# zgrzewarka.net
KiCad netlist of a schematic drawn in EAGLE
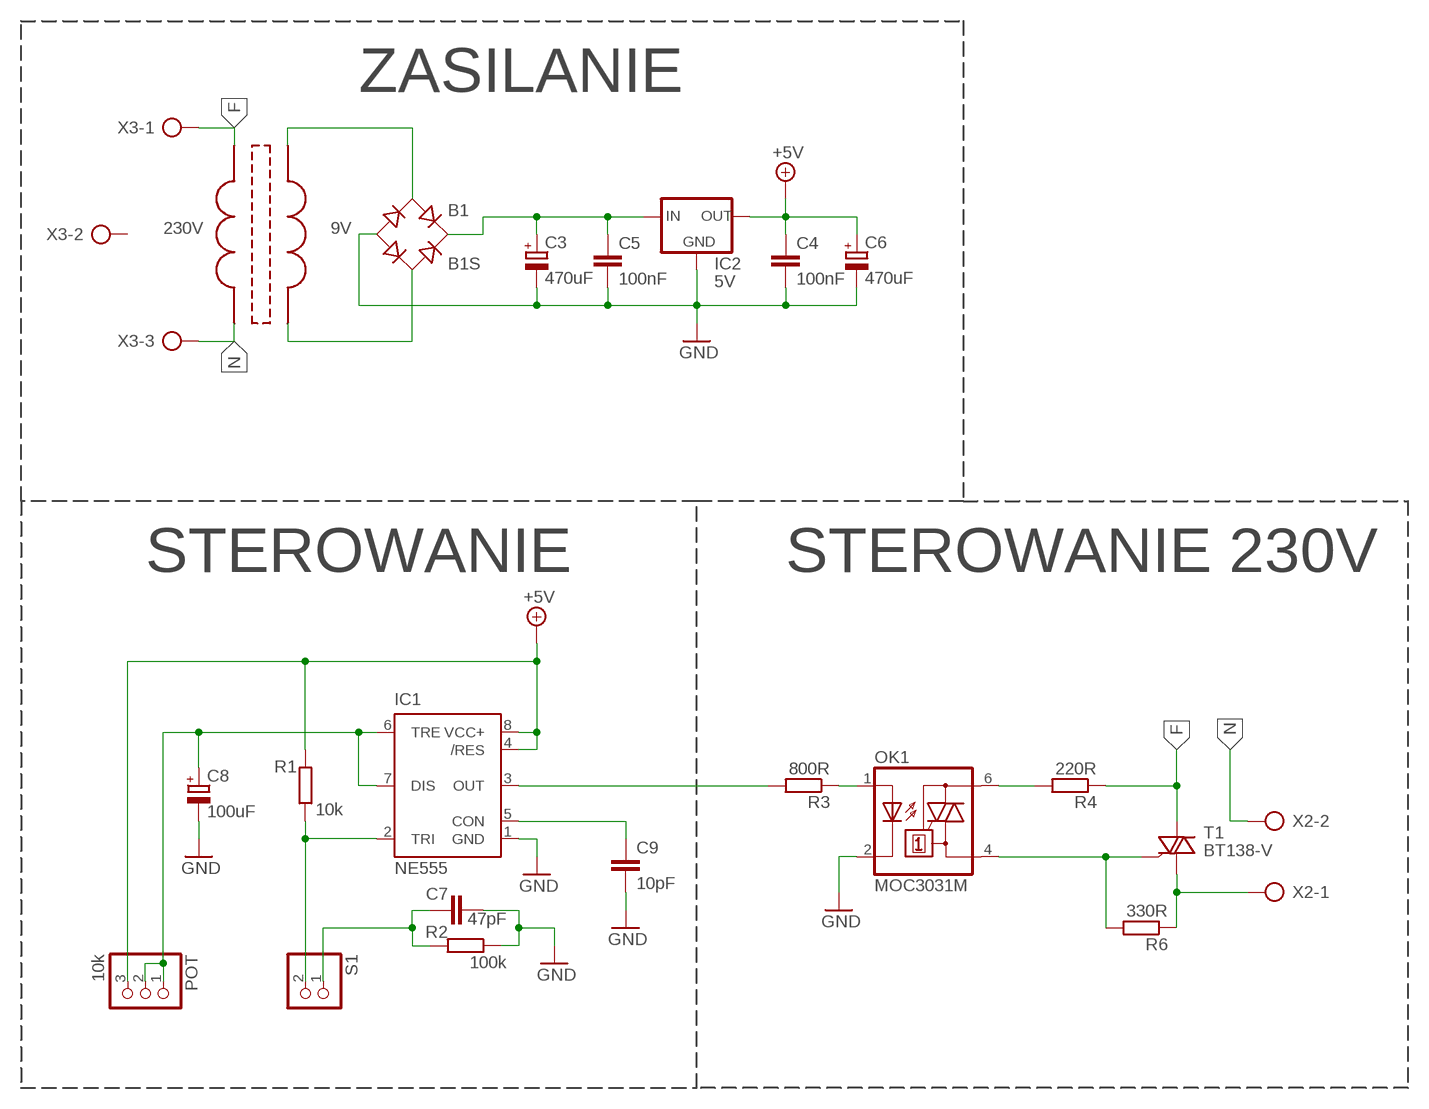
[diagram p0: schematic, sheet 1]

(export (version "E")
  (design (tool "Eeschema 10.0.6"))
  (components
    (comp (ref "B1")
      (value "B1S")
      (footprint "eagle-import:MBS")
      (libsource (lib "eagle-import") (part "BS1"))
    )
    (comp (ref "C3")
      (value "470uF")
      (footprint "eagle-import:C5-8,5")
      (libsource (lib "eagle-import") (part "C-EU-POL'''"))
    )
    (comp (ref "C4")
      (value "100nF")
      (footprint "eagle-import:C50-45-75")
      (libsource (lib "eagle-import") (part "C-EU050-045-075"))
    )
    (comp (ref "C5")
      (value "100nF")
      (footprint "eagle-import:C50-45-75")
      (libsource (lib "eagle-import") (part "C-EU050-045-075"))
    )
    (comp (ref "C6")
      (value "470uF")
      (footprint "eagle-import:C5-8,5")
      (libsource (lib "eagle-import") (part "C-EU-POL'''"))
    )
    (comp (ref "C7")
      (value "47pF")
      (footprint "eagle-import:C50-45-75")
      (libsource (lib "eagle-import") (part "C-EU050-045-075"))
    )
    (comp (ref "C8")
      (value "100uF")
      (footprint "eagle-import:C5-8,5")
      (libsource (lib "eagle-import") (part "C-EU-POL'''"))
    )
    (comp (ref "C9")
      (value "10pF")
      (footprint "eagle-import:C50-45-75")
      (libsource (lib "eagle-import") (part "C-EU050-045-075"))
    )
    (comp (ref "IC1")
      (value "NE555")
      (footprint "eagle-import:DIL-08")
      (fields (field (name "MF") "Arrow Electronics") (field (name "MPN") "NE555N"))
      (libsource (lib "eagle-import") (part "NE555"))
    )
    (comp (ref "IC2")
      (value "5V")
      (footprint "eagle-import:78LXX")
      (libsource (lib "eagle-import") (part "78LXX"))
    )
    (comp (ref "OK1")
      (value "MOC3031M")
      (footprint "eagle-import:DIL06")
      (fields (field (name "MF") "FAIRCHILD SEMICONDUCTOR"))
      (libsource (lib "eagle-import") (part "MOC3031M"))
    )
    (comp (ref "POT")
      (value "10k")
      (footprint "eagle-import:1X03")
      (libsource (lib "eagle-import") (part "PINHD-1X3"))
    )
    (comp (ref "R1")
      (value "10k")
      (footprint "eagle-import:204_7")
      (libsource (lib "eagle-import") (part "R-EU7"))
    )
    (comp (ref "R2")
      (value "100k")
      (footprint "eagle-import:204_7")
      (libsource (lib "eagle-import") (part "R-EU7"))
    )
    (comp (ref "R3")
      (value "800R")
      (footprint "eagle-import:204_7")
      (libsource (lib "eagle-import") (part "R-EU7"))
    )
    (comp (ref "R4")
      (value "220R")
      (footprint "eagle-import:204_7")
      (libsource (lib "eagle-import") (part "R-EU7"))
    )
    (comp (ref "R6")
      (value "330R")
      (footprint "eagle-import:204_7")
      (libsource (lib "eagle-import") (part "R-EU7"))
    )
    (comp (ref "S1")
      (value "PINHD-1X2")
      (footprint "eagle-import:1X02")
      (libsource (lib "eagle-import") (part "PINHD-1X2"))
    )
    (comp (ref "T1")
      (value "BT138-V")
      (footprint "eagle-import:TO220BV")
      (libsource (lib "eagle-import") (part "BT138-V"))
    )
    (comp (ref "U$1")
      (value "TRAFO-9V")
      (footprint "eagle-import:OBUDOWA1")
      (libsource (lib "eagle-import") (part "TRAFO-9V"))
    )
    (comp (ref "X2")
      (value "AK300/2")
      (footprint "eagle-import:AK300_2")
      (libsource (lib "eagle-import") (part "AK300/2"))
    )
    (comp (ref "X3")
      (value "AK300/3")
      (footprint "eagle-import:AK300_3")
      (libsource (lib "eagle-import") (part "AK300/3"))
    )
  )
  (nets
    (net (code "1") (name "+5V") (class "Default")
      (node (ref "C4") (pin "P$1") (pinfunction "1_P$1") (pintype "passive"))
      (node (ref "C6") (pin "+") (pinfunction "+_+") (pintype "passive"))
      (node (ref "IC1") (pin "4") (pinfunction "/RES_4") (pintype "input"))
      (node (ref "IC1") (pin "8") (pinfunction "VCC+_8") (pintype "power_in"))
      (node (ref "IC2") (pin "OUT") (pinfunction "OUT_OUT") (pintype "passive"))
      (node (ref "POT") (pin "3") (pinfunction "3_3") (pintype "passive"))
      (node (ref "R1") (pin "P$2") (pinfunction "2_P$2") (pintype "passive"))
    )
    (net (code "2") (name "F") (class "Default")
      (node (ref "R4") (pin "P$1") (pinfunction "1_P$1") (pintype "passive"))
      (node (ref "T1") (pin "T2") (pinfunction "A2_T2") (pintype "passive"))
      (node (ref "U$1") (pin "230V-1") (pinfunction "230V-1_230V-1") (pintype "bidirectional"))
      (node (ref "X3") (pin "1") (pinfunction "KL_1") (pintype "passive"))
    )
    (net (code "3") (name "GND") (class "Default")
      (node (ref "B1") (pin "-") (pinfunction "-_-") (pintype "passive"))
      (node (ref "C3") (pin "-") (pinfunction "-_-") (pintype "passive"))
      (node (ref "C4") (pin "P$2") (pinfunction "2_P$2") (pintype "passive"))
      (node (ref "C5") (pin "P$2") (pinfunction "2_P$2") (pintype "passive"))
      (node (ref "C6") (pin "-") (pinfunction "-_-") (pintype "passive"))
      (node (ref "C7") (pin "P$2") (pinfunction "2_P$2") (pintype "passive"))
      (node (ref "C8") (pin "-") (pinfunction "-_-") (pintype "passive"))
      (node (ref "C9") (pin "P$2") (pinfunction "2_P$2") (pintype "passive"))
      (node (ref "IC1") (pin "1") (pinfunction "GND_1") (pintype "power_in"))
      (node (ref "IC2") (pin "GND") (pinfunction "GND_GND") (pintype "input"))
      (node (ref "OK1") (pin "2") (pinfunction "C_2") (pintype "passive"))
      (node (ref "R2") (pin "P$1") (pinfunction "1_P$1") (pintype "passive"))
    )
    (net (code "4") (name "N") (class "Default")
      (node (ref "U$1") (pin "230V-2") (pinfunction "230V-2_230V-2") (pintype "bidirectional"))
      (node (ref "X2") (pin "2") (pinfunction "KL_2") (pintype "passive"))
      (node (ref "X3") (pin "3") (pinfunction "KL_3") (pintype "passive"))
    )
    (net (code "5") (name "Net-(B1-PadAC1)") (class "Default")
      (node (ref "B1") (pin "AC1") (pinfunction "AC1_AC1") (pintype "passive"))
      (node (ref "U$1") (pin "9V-1") (pinfunction "9V-1_9V-1") (pintype "bidirectional"))
    )
    (net (code "6") (name "Net-(B1-PadAC2)") (class "Default")
      (node (ref "B1") (pin "AC2") (pinfunction "AC2_AC2") (pintype "passive"))
      (node (ref "U$1") (pin "9V-2") (pinfunction "9V-2_9V-2") (pintype "bidirectional"))
    )
    (net (code "7") (name "Net-(C5-1)") (class "Default")
      (node (ref "B1") (pin "+") (pinfunction "+_+") (pintype "passive"))
      (node (ref "C3") (pin "+") (pinfunction "+_+") (pintype "passive"))
      (node (ref "C5") (pin "P$1") (pinfunction "1_P$1") (pintype "passive"))
      (node (ref "IC2") (pin "IN") (pinfunction "IN_IN") (pintype "input"))
    )
    (net (code "8") (name "Net-(C7-1)") (class "Default")
      (node (ref "C7") (pin "P$1") (pinfunction "1_P$1") (pintype "passive"))
      (node (ref "R2") (pin "P$2") (pinfunction "2_P$2") (pintype "passive"))
      (node (ref "S1") (pin "1") (pinfunction "1_1") (pintype "passive"))
    )
    (net (code "9") (name "Net-(C9-1)") (class "Default")
      (node (ref "C9") (pin "P$1") (pinfunction "1_P$1") (pintype "passive"))
      (node (ref "IC1") (pin "5") (pinfunction "CON_5") (pintype "input"))
    )
    (net (code "10") (name "Net-(IC1-DIS)") (class "Default")
      (node (ref "C8") (pin "+") (pinfunction "+_+") (pintype "passive"))
      (node (ref "IC1") (pin "6") (pinfunction "TRE_6") (pintype "input"))
      (node (ref "IC1") (pin "7") (pinfunction "DIS_7") (pintype "input"))
      (node (ref "POT") (pin "1") (pinfunction "1_1") (pintype "passive"))
      (node (ref "POT") (pin "2") (pinfunction "2_2") (pintype "passive"))
    )
    (net (code "11") (name "Net-(IC1-OUT)") (class "Default")
      (node (ref "IC1") (pin "3") (pinfunction "OUT_3") (pintype "output"))
      (node (ref "R3") (pin "P$2") (pinfunction "2_P$2") (pintype "passive"))
    )
    (net (code "12") (name "Net-(IC1-TRI)") (class "Default")
      (node (ref "IC1") (pin "2") (pinfunction "TRI_2") (pintype "input"))
      (node (ref "R1") (pin "P$1") (pinfunction "1_P$1") (pintype "passive"))
      (node (ref "S1") (pin "2") (pinfunction "2_2") (pintype "passive"))
    )
    (net (code "13") (name "Net-(OK1-A)") (class "Default")
      (node (ref "OK1") (pin "1") (pinfunction "A_1") (pintype "passive"))
      (node (ref "R3") (pin "P$1") (pinfunction "1_P$1") (pintype "passive"))
    )
    (net (code "14") (name "Net-(OK1-A1)") (class "Default")
      (node (ref "OK1") (pin "4") (pinfunction "A1_4") (pintype "passive"))
      (node (ref "R6") (pin "P$2") (pinfunction "2_P$2") (pintype "passive"))
      (node (ref "T1") (pin "G") (pinfunction "G_G") (pintype "passive"))
    )
    (net (code "15") (name "Net-(OK1-A2)") (class "Default")
      (node (ref "OK1") (pin "6") (pinfunction "A2_6") (pintype "passive"))
      (node (ref "R4") (pin "P$2") (pinfunction "2_P$2") (pintype "passive"))
    )
    (net (code "16") (name "Net-(R6-1)") (class "Default")
      (node (ref "R6") (pin "P$1") (pinfunction "1_P$1") (pintype "passive"))
      (node (ref "T1") (pin "T1") (pinfunction "A1_T1") (pintype "passive"))
      (node (ref "X2") (pin "1") (pinfunction "KL_1") (pintype "passive"))
    )
    (net (code "17") (name "unconnected-(X3B-KL-Pad2)") (class "Default")
      (node (ref "X3") (pin "2") (pinfunction "KL_2") (pintype "passive"))
    )
  )
)
